# esp8266-bme280-deepsleep.net
KiCad netlist of a schematic drawn in EAGLE
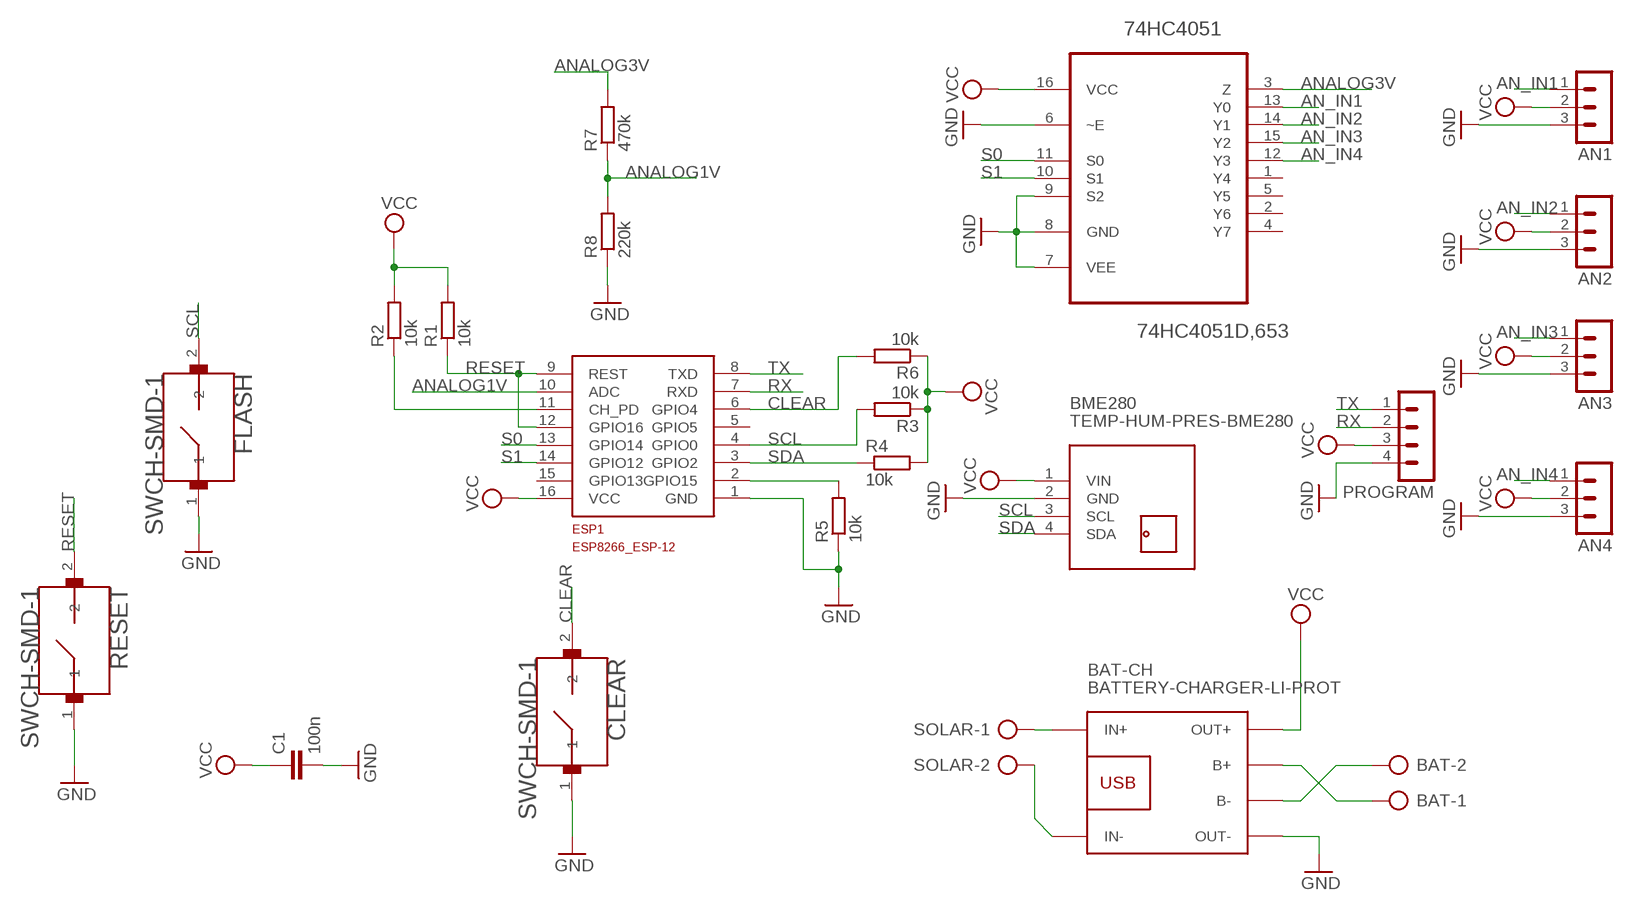
[diagram p0: schematic, sheet 1]

(export (version "E")
  (design (tool "Eeschema 10.0.6"))
  (components
    (comp (ref "74HC4051")
      (value "74HC4051D,653")
      (footprint "eagle-import:SOIC127P600X175-16N")
      (fields (field (name "MF") "Nexperia"))
      (libsource (lib "eagle-import") (part "74HC4051D,653"))
    )
    (comp (ref "AN1")
      (value "MA03-1")
      (footprint "eagle-import:MA03-1")
      (libsource (lib "eagle-import") (part "MA03-1"))
    )
    (comp (ref "AN2")
      (value "MA03-1")
      (footprint "eagle-import:MA03-1")
      (libsource (lib "eagle-import") (part "MA03-1"))
    )
    (comp (ref "AN3")
      (value "MA03-1")
      (footprint "eagle-import:MA03-1")
      (libsource (lib "eagle-import") (part "MA03-1"))
    )
    (comp (ref "AN4")
      (value "MA03-1")
      (footprint "eagle-import:MA03-1")
      (libsource (lib "eagle-import") (part "MA03-1"))
    )
    (comp (ref "BAT")
      (value "PWR_CONN_KK")
      (footprint "eagle-import:PWR_CONN_KK_5MM")
      (libsource (lib "eagle-import") (part "PWR_CONN_KK"))
    )
    (comp (ref "BAT-CH")
      (value "BATTERY-CHARGER-LI-PROT")
      (footprint "eagle-import:BATTERY-CHARGER-LI-PROT")
      (libsource (lib "eagle-import") (part "BATTERY-CHARGER-LI-PROT"))
    )
    (comp (ref "BME280")
      (value "TEMP-HUM-PRES-BME280")
      (footprint "eagle-import:TEMP-HUM-PRES-BME280")
      (libsource (lib "eagle-import") (part "TEMP-HUM-PRES-BME280"))
    )
    (comp (ref "C1")
      (value "100n")
      (footprint "eagle-import:C2.5-3")
      (libsource (lib "eagle-import") (part "C2,5-3"))
    )
    (comp (ref "CLEAR")
      (value "SWCH-SMD-1")
      (footprint "eagle-import:SWCH-SMD-1")
      (fields (field (name "MF") "Omron") (field (name "MP") "B3U-1000P"))
      (libsource (lib "eagle-import") (part "SWCH-SMD-1"))
    )
    (comp (ref "ESP1")
      (value "ESP8266_ESP-12")
      (footprint "eagle-import:ESP8266-ESP12")
      (libsource (lib "eagle-import") (part "ESP8266_ESP-12"))
    )
    (comp (ref "FLASH")
      (value "SWCH-SMD-1")
      (footprint "eagle-import:SWCH-SMD-1")
      (fields (field (name "MF") "Omron") (field (name "MP") "B3U-1000P"))
      (libsource (lib "eagle-import") (part "SWCH-SMD-1"))
    )
    (comp (ref "PROGRAM")
      (value "MA04-1")
      (footprint "eagle-import:MA04-1")
      (libsource (lib "eagle-import") (part "MA04-1"))
    )
    (comp (ref "R1")
      (value "10k")
      (footprint "eagle-import:0204_7")
      (libsource (lib "eagle-import") (part "R-EU_0204/7"))
    )
    (comp (ref "R2")
      (value "10k")
      (footprint "eagle-import:0204_7")
      (libsource (lib "eagle-import") (part "R-EU_0204/7"))
    )
    (comp (ref "R3")
      (value "10k")
      (footprint "eagle-import:0204_7")
      (libsource (lib "eagle-import") (part "R-EU_0204/7"))
    )
    (comp (ref "R4")
      (value "10k")
      (footprint "eagle-import:0204_7")
      (libsource (lib "eagle-import") (part "R-EU_0204/7"))
    )
    (comp (ref "R5")
      (value "10k")
      (footprint "eagle-import:0204_7")
      (libsource (lib "eagle-import") (part "R-EU_0204/7"))
    )
    (comp (ref "R6")
      (value "10k")
      (footprint "eagle-import:0204_7")
      (libsource (lib "eagle-import") (part "R-EU_0204/7"))
    )
    (comp (ref "R7")
      (value "470k")
      (footprint "eagle-import:0204_7")
      (libsource (lib "eagle-import") (part "R-EU_0204/7"))
    )
    (comp (ref "R8")
      (value "220k")
      (footprint "eagle-import:0204_7")
      (libsource (lib "eagle-import") (part "R-EU_0204/7"))
    )
    (comp (ref "RESET")
      (value "SWCH-SMD-1")
      (footprint "eagle-import:SWCH-SMD-1")
      (fields (field (name "MF") "Omron") (field (name "MP") "B3U-1000P"))
      (libsource (lib "eagle-import") (part "SWCH-SMD-1"))
    )
    (comp (ref "SOLAR")
      (value "PWR_CONN_KK")
      (footprint "eagle-import:PWR_CONN_KK_5MM")
      (libsource (lib "eagle-import") (part "PWR_CONN_KK"))
    )
  )
  (nets
    (net (code "1") (name "/ANALOG1V") (class "Default")
      (node (ref "ESP1") (pin "10") (pinfunction "ADC_10") (pintype "bidirectional"))
      (node (ref "R7") (pin "1") (pinfunction "1_1") (pintype "passive"))
      (node (ref "R8") (pin "2") (pinfunction "2_2") (pintype "passive"))
    )
    (net (code "2") (name "/ANALOG3V") (class "Default")
      (node (ref "74HC4051") (pin "3") (pinfunction "Z_3") (pintype "bidirectional"))
      (node (ref "R7") (pin "2") (pinfunction "2_2") (pintype "passive"))
    )
    (net (code "3") (name "/AN_IN1") (class "Default")
      (node (ref "74HC4051") (pin "13") (pinfunction "Y0_13") (pintype "bidirectional"))
      (node (ref "AN1") (pin "1") (pinfunction "1_1") (pintype "passive"))
    )
    (net (code "4") (name "/AN_IN2") (class "Default")
      (node (ref "74HC4051") (pin "14") (pinfunction "Y1_14") (pintype "bidirectional"))
      (node (ref "AN2") (pin "1") (pinfunction "1_1") (pintype "passive"))
    )
    (net (code "5") (name "/AN_IN3") (class "Default")
      (node (ref "74HC4051") (pin "15") (pinfunction "Y2_15") (pintype "bidirectional"))
      (node (ref "AN3") (pin "1") (pinfunction "1_1") (pintype "passive"))
    )
    (net (code "6") (name "/AN_IN4") (class "Default")
      (node (ref "74HC4051") (pin "12") (pinfunction "Y3_12") (pintype "bidirectional"))
      (node (ref "AN4") (pin "1") (pinfunction "1_1") (pintype "passive"))
    )
    (net (code "7") (name "/CLEAR") (class "Default")
      (node (ref "CLEAR") (pin "2") (pinfunction "2_2") (pintype "passive"))
      (node (ref "ESP1") (pin "6") (pinfunction "GPIO4_6") (pintype "bidirectional"))
      (node (ref "R6") (pin "2") (pinfunction "2_2") (pintype "passive"))
    )
    (net (code "8") (name "/RESET") (class "Default")
      (node (ref "ESP1") (pin "12") (pinfunction "GPIO16_12") (pintype "bidirectional"))
      (node (ref "ESP1") (pin "9") (pinfunction "REST_9") (pintype "bidirectional"))
      (node (ref "R1") (pin "1") (pinfunction "1_1") (pintype "passive"))
      (node (ref "RESET") (pin "2") (pinfunction "2_2") (pintype "passive"))
    )
    (net (code "9") (name "/RX") (class "Default")
      (node (ref "ESP1") (pin "7") (pinfunction "RXD_7") (pintype "bidirectional"))
      (node (ref "PROGRAM") (pin "2") (pinfunction "2_2") (pintype "passive"))
    )
    (net (code "10") (name "/S0") (class "Default")
      (node (ref "74HC4051") (pin "11") (pinfunction "S0_11") (pintype "input"))
      (node (ref "ESP1") (pin "13") (pinfunction "GPIO14_13") (pintype "bidirectional"))
    )
    (net (code "11") (name "/S1") (class "Default")
      (node (ref "74HC4051") (pin "10") (pinfunction "S1_10") (pintype "input"))
      (node (ref "ESP1") (pin "14") (pinfunction "GPIO12_14") (pintype "bidirectional"))
    )
    (net (code "12") (name "/SCL") (class "Default")
      (node (ref "BME280") (pin "3") (pinfunction "SCL_3") (pintype "bidirectional"))
      (node (ref "ESP1") (pin "4") (pinfunction "GPIO0_4") (pintype "bidirectional"))
      (node (ref "FLASH") (pin "2") (pinfunction "2_2") (pintype "passive"))
      (node (ref "R3") (pin "2") (pinfunction "2_2") (pintype "passive"))
    )
    (net (code "13") (name "/SDA") (class "Default")
      (node (ref "BME280") (pin "4") (pinfunction "SDA_4") (pintype "bidirectional"))
      (node (ref "ESP1") (pin "3") (pinfunction "GPIO2_3") (pintype "bidirectional"))
      (node (ref "R4") (pin "1") (pinfunction "1_1") (pintype "passive"))
    )
    (net (code "14") (name "/TX") (class "Default")
      (node (ref "ESP1") (pin "8") (pinfunction "TXD_8") (pintype "bidirectional"))
      (node (ref "PROGRAM") (pin "1") (pinfunction "1_1") (pintype "passive"))
    )
    (net (code "15") (name "GND") (class "Default")
      (node (ref "74HC4051") (pin "6") (pinfunction "~{E}_6") (pintype "input"))
      (node (ref "74HC4051") (pin "7") (pinfunction "VEE_7") (pintype "power_in"))
      (node (ref "74HC4051") (pin "8") (pinfunction "GND_8") (pintype "passive"))
      (node (ref "74HC4051") (pin "9") (pinfunction "S2_9") (pintype "input"))
      (node (ref "AN1") (pin "3") (pinfunction "3_3") (pintype "passive"))
      (node (ref "AN2") (pin "3") (pinfunction "3_3") (pintype "passive"))
      (node (ref "AN3") (pin "3") (pinfunction "3_3") (pintype "passive"))
      (node (ref "AN4") (pin "3") (pinfunction "3_3") (pintype "passive"))
      (node (ref "BAT-CH") (pin "OUT-") (pinfunction "OUT-_OUT-") (pintype "bidirectional"))
      (node (ref "BME280") (pin "2") (pinfunction "GND_2") (pintype "power_in"))
      (node (ref "C1") (pin "2") (pinfunction "2_2") (pintype "passive"))
      (node (ref "CLEAR") (pin "1") (pinfunction "1_1") (pintype "passive"))
      (node (ref "ESP1") (pin "1") (pinfunction "GND_1") (pintype "bidirectional"))
      (node (ref "FLASH") (pin "1") (pinfunction "1_1") (pintype "passive"))
      (node (ref "PROGRAM") (pin "4") (pinfunction "4_4") (pintype "passive"))
      (node (ref "R5") (pin "1") (pinfunction "1_1") (pintype "passive"))
      (node (ref "R8") (pin "1") (pinfunction "1_1") (pintype "passive"))
      (node (ref "RESET") (pin "1") (pinfunction "1_1") (pintype "passive"))
    )
    (net (code "16") (name "Net-(BATA-KL)") (class "Default")
      (node (ref "BAT") (pin "1") (pinfunction "KL_1") (pintype "passive"))
      (node (ref "BAT-CH") (pin "B+") (pinfunction "B+_B+") (pintype "bidirectional"))
    )
    (net (code "17") (name "Net-(BATB-KL)") (class "Default")
      (node (ref "BAT") (pin "2") (pinfunction "KL_2") (pintype "passive"))
      (node (ref "BAT-CH") (pin "B-") (pinfunction "B-_B-") (pintype "bidirectional"))
    )
    (net (code "18") (name "Net-(ESP1-CH_PD)") (class "Default")
      (node (ref "ESP1") (pin "11") (pinfunction "CH_PD_11") (pintype "bidirectional"))
      (node (ref "R2") (pin "1") (pinfunction "1_1") (pintype "passive"))
    )
    (net (code "19") (name "Net-(ESP1-GPIO15)") (class "Default")
      (node (ref "ESP1") (pin "2") (pinfunction "GPIO15_2") (pintype "bidirectional"))
      (node (ref "R5") (pin "2") (pinfunction "2_2") (pintype "passive"))
    )
    (net (code "20") (name "Net-(SOLARA-KL)") (class "Default")
      (node (ref "BAT-CH") (pin "IN+") (pinfunction "IN+_IN+") (pintype "bidirectional"))
      (node (ref "SOLAR") (pin "1") (pinfunction "KL_1") (pintype "passive"))
    )
    (net (code "21") (name "Net-(SOLARB-KL)") (class "Default")
      (node (ref "BAT-CH") (pin "IN-") (pinfunction "IN-_IN-") (pintype "bidirectional"))
      (node (ref "SOLAR") (pin "2") (pinfunction "KL_2") (pintype "passive"))
    )
    (net (code "22") (name "VCC") (class "Default")
      (node (ref "74HC4051") (pin "16") (pinfunction "VCC_16") (pintype "power_in"))
      (node (ref "AN1") (pin "2") (pinfunction "2_2") (pintype "passive"))
      (node (ref "AN2") (pin "2") (pinfunction "2_2") (pintype "passive"))
      (node (ref "AN3") (pin "2") (pinfunction "2_2") (pintype "passive"))
      (node (ref "AN4") (pin "2") (pinfunction "2_2") (pintype "passive"))
      (node (ref "BAT-CH") (pin "OUT+") (pinfunction "OUT+_OUT+") (pintype "bidirectional"))
      (node (ref "BME280") (pin "1") (pinfunction "VIN_1") (pintype "power_in"))
      (node (ref "C1") (pin "1") (pinfunction "1_1") (pintype "passive"))
      (node (ref "ESP1") (pin "16") (pinfunction "VCC_16") (pintype "bidirectional"))
      (node (ref "PROGRAM") (pin "3") (pinfunction "3_3") (pintype "passive"))
      (node (ref "R1") (pin "2") (pinfunction "2_2") (pintype "passive"))
      (node (ref "R2") (pin "2") (pinfunction "2_2") (pintype "passive"))
      (node (ref "R3") (pin "1") (pinfunction "1_1") (pintype "passive"))
      (node (ref "R4") (pin "2") (pinfunction "2_2") (pintype "passive"))
      (node (ref "R6") (pin "1") (pinfunction "1_1") (pintype "passive"))
    )
    (net (code "23") (name "unconnected-(74HC4051-Y4-Pad1)") (class "Default")
      (node (ref "74HC4051") (pin "1") (pinfunction "Y4_1") (pintype "bidirectional"))
    )
    (net (code "24") (name "unconnected-(74HC4051-Y5-Pad5)") (class "Default")
      (node (ref "74HC4051") (pin "5") (pinfunction "Y5_5") (pintype "bidirectional"))
    )
    (net (code "25") (name "unconnected-(74HC4051-Y6-Pad2)") (class "Default")
      (node (ref "74HC4051") (pin "2") (pinfunction "Y6_2") (pintype "bidirectional"))
    )
    (net (code "26") (name "unconnected-(74HC4051-Y7-Pad4)") (class "Default")
      (node (ref "74HC4051") (pin "4") (pinfunction "Y7_4") (pintype "bidirectional"))
    )
    (net (code "27") (name "unconnected-(ESP1-GPIO5-Pad5)") (class "Default")
      (node (ref "ESP1") (pin "5") (pinfunction "GPIO5_5") (pintype "bidirectional"))
    )
    (net (code "28") (name "unconnected-(ESP1-GPIO13-Pad15)") (class "Default")
      (node (ref "ESP1") (pin "15") (pinfunction "GPIO13_15") (pintype "bidirectional"))
    )
  )
)
